# Buck_Converter.net
KiCad netlist of a schematic drawn in Altium Designer
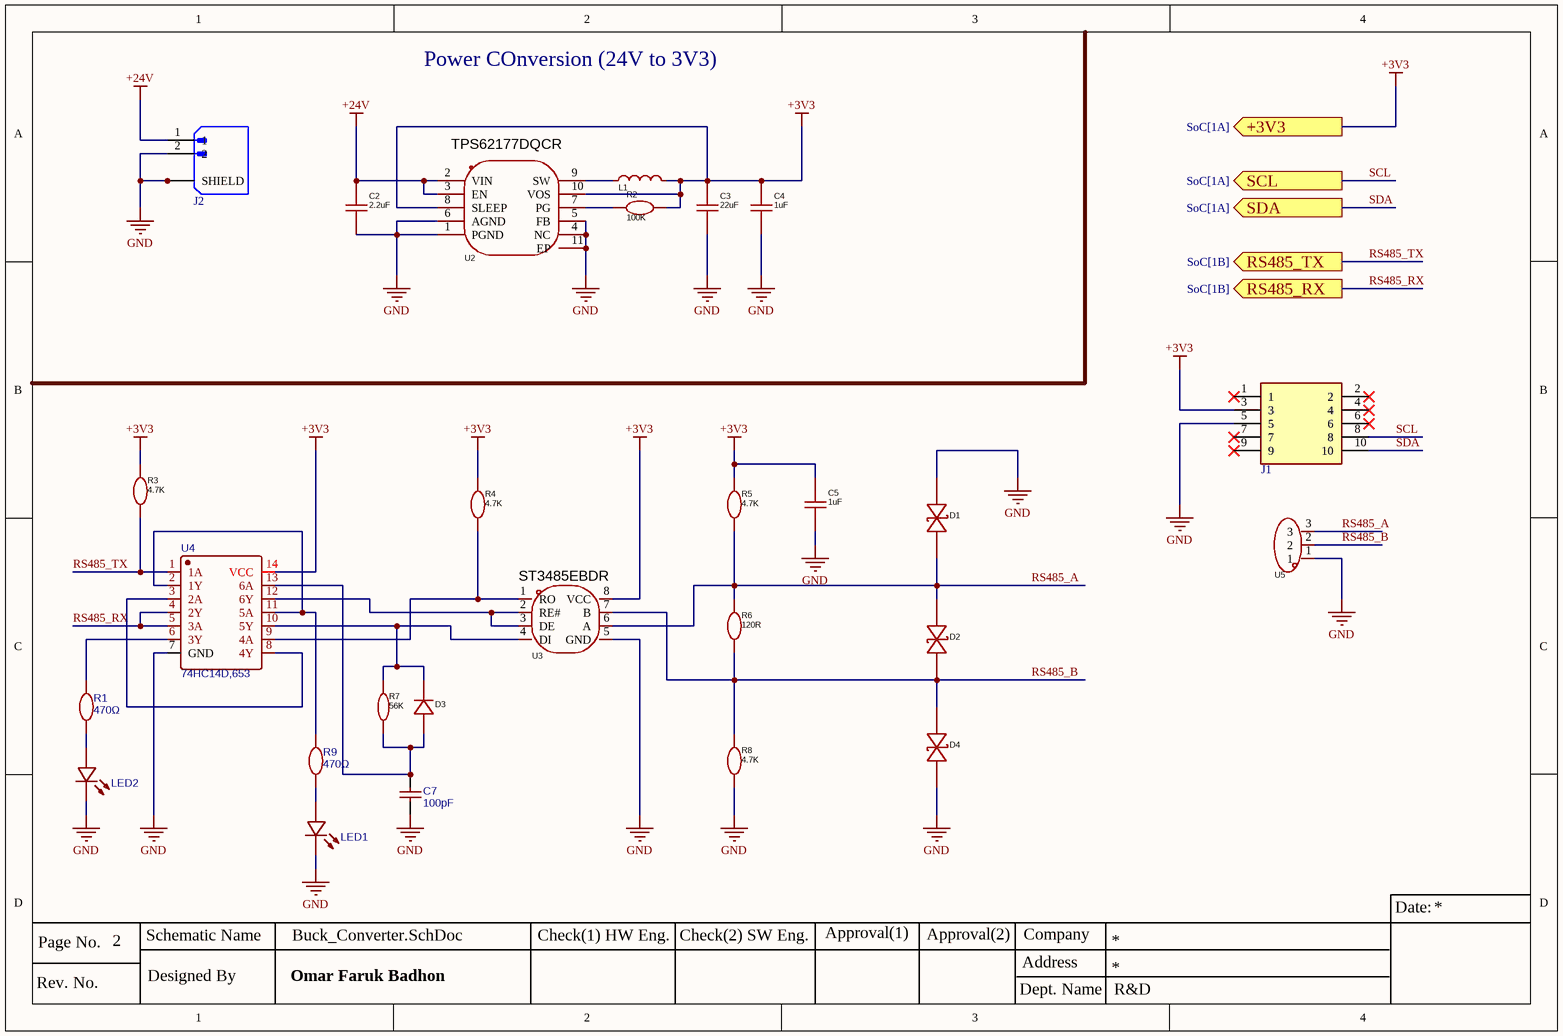
[diagram p0: Buck_Converter.SchDoc]

(export (version "E")
  (design (tool "Eeschema 10.0.6"))
  (components
    (comp (ref "C2")
      (value "2.2uF")
      (footprint "Cap 2.2uF")
      (description "Cap 2.2uF 35V")
      (fields
        (field (name "MANUFACTURER") "muRata(村田)")
        (field (name "MANUFACTURER PART") "GRM155R6YA225KE11D")
      )
      (libsource (lib "Sch lib") (part "GRM155R6YA225KE11D"))
    )
    (comp (ref "C3")
      (value "22uF")
      (footprint "Cap 22uF")
      (description "Cap 22uF 16V")
      (fields
        (field (name "MANUFACTURER") "muRata(村田)")
        (field (name "MANUFACTURER PART") "GRM21BC81C226ME44L")
      )
      (libsource (lib "Sch lib") (part "GRM21BC81C226ME44L"))
    )
    (comp (ref "C4")
      (value "1uF")
      (footprint "Cap 1uF")
      (description "Cap 1uF 16V")
      (fields
        (field (name "MANUFACTURER") "muRata(村田)")
        (field (name "MANUFACTURER PART") "GCM188R71C105KA64D")
      )
      (libsource (lib "Sch lib") (part "GCM188R71C105KA64D"))
    )
    (comp (ref "C5")
      (value "1uF")
      (footprint "Cap 1uF")
      (description "Cap 1uF 16V")
      (fields
        (field (name "MANUFACTURER") "muRata(村田)")
        (field (name "MANUFACTURER PART") "GCM188R71C105KA64D")
      )
      (libsource (lib "Sch lib") (part "GCM188R71C105KA64D"))
    )
    (comp (ref "C7")
      (value "100pF")
      (footprint "Cap 100pF")
      (description "Cap 100pF 50V")
      (fields
        (field (name "MANUFACTURER") "muRata(村田)")
        (field (name "MANUFACTURER PART") "GCM1885C1H101JA16D")
      )
      (libsource (lib "Sch lib") (part "100pF"))
    )
    (comp (ref "D1")
      (value "SMAJ58CA")
      (footprint "TVS diode")
      (fields (field (name "MANUFACTURER") "Littelfuse(美国力特)"))
      (libsource (lib "Sch lib") (part "SMAJ58CA_C148235"))
    )
    (comp (ref "D2")
      (value "SMAJ58CA")
      (footprint "TVS diode")
      (fields (field (name "MANUFACTURER") "Littelfuse(美国力特)"))
      (libsource (lib "Sch lib") (part "SMAJ58CA_C148235"))
    )
    (comp (ref "D3")
      (value "1N4148W")
      (footprint "1N4148W")
      (fields (field (name "MANUFACTURER") "Agertech(艾吉芯)"))
      (libsource (lib "Sch lib") (part "1N4148W"))
    )
    (comp (ref "D4")
      (value "SMAJ58CA")
      (footprint "TVS diode")
      (fields (field (name "MANUFACTURER") "Littelfuse(美国力特)"))
      (libsource (lib "Sch lib") (part "SMAJ58CA_C148235"))
    )
    (comp (ref "J1")
      (value "CLP-105-02-L-D")
      (footprint "Sesnor Connector")
      (libsource (lib "Sch lib") (part "CLP-105-02-L-D"))
    )
    (comp (ref "J2")
      (value "Power Connector")
      (footprint "Power Connector")
      (description "Picoblade Connector, 2 Circuit Single Row, Right Angle Surface Mount SMT PCB")
      (fields (field (name "MF") "{'manufacturer': u'Molex'}") (field (name "MP") "0532610271"))
      (libsource (lib "Sch lib") (part "Power Connector"))
    )
    (comp (ref "L1")
      (value "LPS4018-103MRC")
      (footprint "Inductor")
      (description "Inductor 10uH")
      (fields (field (name "MANUFACTURER") "Coilcraft(线艺)"))
      (libsource (lib "Sch lib") (part "LPS4018-103MRC"))
    )
    (comp (ref "LED1")
      (value "VLMS1300-GS08")
      (footprint "LED")
      (description "Led")
      (fields (field (name "MANUFACTURER") "VISHAY(威世)") (field (name "CONTRIBUTOR") "LCSC"))
      (libsource (lib "Sch lib") (part "VLMS1300-GS08"))
    )
    (comp (ref "LED2")
      (value "VLMS1300-GS08")
      (footprint "LED")
      (description "Led")
      (fields (field (name "MANUFACTURER") "VISHAY(威世)") (field (name "CONTRIBUTOR") "LCSC"))
      (libsource (lib "Sch lib") (part "VLMS1300-GS08"))
    )
    (comp (ref "R1")
      (value "470Ω")
      (footprint "Res 470R")
      (description "Res 470R")
      (fields
        (field (name "MANUFACTURER") "PANASONIC(松下)")
        (field (name "MANUFACTURER PART") "ERJPA3F4700V")
        (field (name "CONTRIBUTOR") "lcsc")
      )
      (libsource (lib "Sch lib") (part "470Ω"))
    )
    (comp (ref "R2")
      (value "100K")
      (footprint "Res 100K")
      (description "Res 100K 50V")
      (fields (field (name "MANUFACTURER") "PANASONIC(松下)") (field (name "MANUFACTURER PART") "ERA2AEB104X"))
      (libsource (lib "Sch lib") (part "ERA2AEB104X"))
    )
    (comp (ref "R3")
      (value "4.7K")
      (footprint "Res 4.7K")
      (description "Res 4.7K")
      (fields (field (name "MANUFACTURER") "PANASONIC(松下)") (field (name "MANUFACTURER PART") "ERJPA3F4701V"))
      (libsource (lib "Sch lib") (part "ERJPA3F4701V"))
    )
    (comp (ref "R4")
      (value "4.7K")
      (footprint "Res 4.7K")
      (description "Res 4.7K")
      (fields (field (name "MANUFACTURER") "PANASONIC(松下)") (field (name "MANUFACTURER PART") "ERJPA3F4701V"))
      (libsource (lib "Sch lib") (part "ERJPA3F4701V"))
    )
    (comp (ref "R5")
      (value "4.7K")
      (footprint "Res 4.7K")
      (description "Res 4.7K")
      (fields (field (name "MANUFACTURER") "PANASONIC(松下)") (field (name "MANUFACTURER PART") "ERJPA3F4701V"))
      (libsource (lib "Sch lib") (part "ERJPA3F4701V"))
    )
    (comp (ref "R6")
      (value "120R")
      (footprint "Res 120R")
      (description "Res 120R")
      (fields (field (name "MANUFACTURER") "PANASONIC(松下)") (field (name "MANUFACTURER PART") "ERJPA3F1200V"))
      (libsource (lib "Sch lib") (part "ERJPA3F1200V"))
    )
    (comp (ref "R7")
      (value "56K")
      (footprint "Rs 56K")
      (description "Res 56K")
      (fields (field (name "MANUFACTURER") "PANASONIC(松下)") (field (name "MANUFACTURER PART") "ERJ3EKF5602V"))
      (libsource (lib "Sch lib") (part "ERJ3EKF5602V"))
    )
    (comp (ref "R8")
      (value "4.7K")
      (footprint "Res 4.7K")
      (description "Res 4.7K")
      (fields (field (name "MANUFACTURER") "PANASONIC(松下)") (field (name "MANUFACTURER PART") "ERJPA3F4701V"))
      (libsource (lib "Sch lib") (part "ERJPA3F4701V"))
    )
    (comp (ref "R9")
      (value "470Ω")
      (footprint "Res 470R")
      (description "Res 470R")
      (fields
        (field (name "MANUFACTURER") "PANASONIC(松下)")
        (field (name "MANUFACTURER PART") "ERJPA3F4700V")
        (field (name "CONTRIBUTOR") "lcsc")
      )
      (libsource (lib "Sch lib") (part "470Ω"))
    )
    (comp (ref "U2")
      (value "TPS62177DQCR")
      (footprint "TPS62177DQCR")
      (fields (field (name "MANUFACTURER") "TI(德州仪器)"))
      (libsource (lib "Sch lib") (part "TPS62177DQCR"))
    )
    (comp (ref "U3")
      (value "ST3485EBDR")
      (footprint "ST3485EBDR")
      (fields (field (name "MANUFACTURER") "ST(意法半导体)"))
      (libsource (lib "Sch lib") (part "ST3485EBDR"))
    )
    (comp (ref "U4")
      (value "74HC14D,653")
      (footprint "74HC14D")
      (fields (field (name "MANUFACTURER") "Nexperia(安世)"))
      (libsource (lib "Sch lib") (part "74HC14D,653"))
    )
    (comp (ref "U5")
      (value "733-363")
      (footprint "RS485 connector")
      (description "6A 3 Straight Needle -60℃~+100℃ 1 2.5mm Gray Plugin,P=2.5mm  Pluggable System Terminal Block ROHS")
      (fields (field (name "MANUFACTURER") "WAGO(万可)"))
      (libsource (lib "Sch lib") (part "RS485 Connector"))
    )
  )
  (nets
    (net (code "1") (name "+3V3") (class "Default")
      (node (ref "C3") (pin "2") (pinfunction "2_2") (pintype "passive"))
      (node (ref "C4") (pin "2") (pinfunction "2_2") (pintype "passive"))
      (node (ref "C5") (pin "2") (pinfunction "2_2") (pintype "passive"))
      (node (ref "J1") (pin "3") (pinfunction "3_3") (pintype "passive"))
      (node (ref "L1") (pin "2") (pinfunction "2_2") (pintype "passive"))
      (node (ref "R2") (pin "2") (pinfunction "2_2") (pintype "passive"))
      (node (ref "R3") (pin "2") (pinfunction "2_2") (pintype "passive"))
      (node (ref "R4") (pin "2") (pinfunction "2_2") (pintype "passive"))
      (node (ref "R5") (pin "2") (pinfunction "2_2") (pintype "passive"))
      (node (ref "U2") (pin "10") (pinfunction "VOS_10") (pintype "passive"))
      (node (ref "U2") (pin "8") (pinfunction "SLEEP_8") (pintype "passive"))
      (node (ref "U3") (pin "8") (pinfunction "VCC_8") (pintype "passive"))
      (node (ref "U4") (pin "14") (pinfunction "VCC_14") (pintype "passive"))
    )
    (net (code "2") (name "+24V") (class "Default")
      (node (ref "C2") (pin "2") (pinfunction "2_2") (pintype "passive"))
      (node (ref "J2") (pin "1") (pinfunction "1_1") (pintype "passive"))
      (node (ref "U2") (pin "2") (pinfunction "VIN_2") (pintype "passive"))
      (node (ref "U2") (pin "3") (pinfunction "EN_3") (pintype "passive"))
    )
    (net (code "3") (name "/RS485_A") (class "Default")
      (node (ref "D1") (pin "1") (pinfunction "1_1") (pintype "passive"))
      (node (ref "D2") (pin "2") (pinfunction "2_2") (pintype "passive"))
      (node (ref "R5") (pin "1") (pinfunction "1_1") (pintype "passive"))
      (node (ref "R6") (pin "2") (pinfunction "2_2") (pintype "passive"))
      (node (ref "U3") (pin "6") (pinfunction "A_6") (pintype "passive"))
      (node (ref "U5") (pin "3") (pinfunction "3_3") (pintype "passive"))
    )
    (net (code "4") (name "/RS485_B") (class "Default")
      (node (ref "D2") (pin "1") (pinfunction "1_1") (pintype "passive"))
      (node (ref "D4") (pin "2") (pinfunction "2_2") (pintype "passive"))
      (node (ref "R6") (pin "1") (pinfunction "1_1") (pintype "passive"))
      (node (ref "R8") (pin "2") (pinfunction "2_2") (pintype "passive"))
      (node (ref "U3") (pin "7") (pinfunction "B_7") (pintype "passive"))
      (node (ref "U5") (pin "2") (pinfunction "2_2") (pintype "passive"))
    )
    (net (code "5") (name "/RS485_RX") (class "Default")
      (node (ref "U4") (pin "4") (pinfunction "2Y_4") (pintype "passive"))
      (node (ref "U4") (pin "5") (pinfunction "3A_5") (pintype "passive"))
    )
    (net (code "6") (name "/RS485_TX") (class "Default")
      (node (ref "R3") (pin "1") (pinfunction "1_1") (pintype "passive"))
      (node (ref "U4") (pin "1") (pinfunction "1A_1") (pintype "passive"))
    )
    (net (code "7") (name "/SCL") (class "Default")
      (node (ref "J1") (pin "8") (pinfunction "8_8") (pintype "passive"))
    )
    (net (code "8") (name "/SDA") (class "Default")
      (node (ref "J1") (pin "10") (pinfunction "10_10") (pintype "passive"))
    )
    (net (code "9") (name "GND") (class "Default")
      (node (ref "C2") (pin "1") (pinfunction "1_1") (pintype "passive"))
      (node (ref "C3") (pin "1") (pinfunction "1_1") (pintype "passive"))
      (node (ref "C4") (pin "1") (pinfunction "1_1") (pintype "passive"))
      (node (ref "C5") (pin "1") (pinfunction "1_1") (pintype "passive"))
      (node (ref "C7") (pin "1") (pinfunction "1_1") (pintype "passive"))
      (node (ref "D1") (pin "2") (pinfunction "2_2") (pintype "passive"))
      (node (ref "D4") (pin "1") (pinfunction "1_1") (pintype "passive"))
      (node (ref "J1") (pin "5") (pinfunction "5_5") (pintype "passive"))
      (node (ref "J2") (pin "2") (pinfunction "2_2") (pintype "passive"))
      (node (ref "J2") (pin "S1") (pinfunction "SHIELD_S1") (pintype "passive"))
      (node (ref "J2") (pin "S2") (pinfunction "SHIELD_S2") (pintype "passive"))
      (node (ref "LED1") (pin "2") (pinfunction "C_2") (pintype "passive"))
      (node (ref "LED2") (pin "2") (pinfunction "C_2") (pintype "passive"))
      (node (ref "R8") (pin "1") (pinfunction "1_1") (pintype "passive"))
      (node (ref "U2") (pin "1") (pinfunction "PGND_1") (pintype "passive"))
      (node (ref "U2") (pin "11") (pinfunction "EP_11") (pintype "passive"))
      (node (ref "U2") (pin "4") (pinfunction "NC_4") (pintype "passive"))
      (node (ref "U2") (pin "5") (pinfunction "FB_5") (pintype "passive"))
      (node (ref "U2") (pin "6") (pinfunction "AGND_6") (pintype "passive"))
      (node (ref "U3") (pin "5") (pinfunction "GND_5") (pintype "passive"))
      (node (ref "U4") (pin "7") (pinfunction "GND_7") (pintype "passive"))
      (node (ref "U5") (pin "1") (pinfunction "1_1") (pintype "passive"))
    )
    (net (code "10") (name "Net-(D3-A)") (class "Default")
      (node (ref "C7") (pin "2") (pinfunction "2_2") (pintype "passive"))
      (node (ref "D3") (pin "2") (pinfunction "A_2") (pintype "passive"))
      (node (ref "R7") (pin "1") (pinfunction "1_1") (pintype "passive"))
      (node (ref "U4") (pin "13") (pinfunction "6A_13") (pintype "passive"))
    )
    (net (code "11") (name "Net-(D3-K)") (class "Default")
      (node (ref "D3") (pin "1") (pinfunction "K_1") (pintype "passive"))
      (node (ref "R7") (pin "2") (pinfunction "2_2") (pintype "passive"))
      (node (ref "U3") (pin "4") (pinfunction "DI_4") (pintype "passive"))
      (node (ref "U4") (pin "10") (pinfunction "5Y_10") (pintype "passive"))
    )
    (net (code "12") (name "Net-(LED1-A)") (class "Default")
      (node (ref "LED1") (pin "1") (pinfunction "A_1") (pintype "passive"))
      (node (ref "R9") (pin "1") (pinfunction "1_1") (pintype "passive"))
    )
    (net (code "13") (name "Net-(LED2-A)") (class "Default")
      (node (ref "LED2") (pin "1") (pinfunction "A_1") (pintype "passive"))
      (node (ref "R1") (pin "1") (pinfunction "1_1") (pintype "passive"))
    )
    (net (code "14") (name "Net-(U2-PG)") (class "Default")
      (node (ref "R2") (pin "1") (pinfunction "1_1") (pintype "passive"))
      (node (ref "U2") (pin "7") (pinfunction "PG_7") (pintype "passive"))
    )
    (net (code "15") (name "Net-(U2-SW)") (class "Default")
      (node (ref "L1") (pin "1") (pinfunction "1_1") (pintype "passive"))
      (node (ref "U2") (pin "9") (pinfunction "SW_9") (pintype "passive"))
    )
    (net (code "16") (name "Net-(U3-DE)") (class "Default")
      (node (ref "U3") (pin "2") (pinfunction "RE#_2") (pintype "passive"))
      (node (ref "U3") (pin "3") (pinfunction "DE_3") (pintype "passive"))
      (node (ref "U4") (pin "12") (pinfunction "6Y_12") (pintype "passive"))
    )
    (net (code "17") (name "Net-(U3-RO)") (class "Default")
      (node (ref "R4") (pin "1") (pinfunction "1_1") (pintype "passive"))
      (node (ref "U3") (pin "1") (pinfunction "RO_1") (pintype "passive"))
      (node (ref "U4") (pin "9") (pinfunction "4A_9") (pintype "passive"))
    )
    (net (code "18") (name "Net-(U4-1Y)") (class "Default")
      (node (ref "R9") (pin "2") (pinfunction "2_2") (pintype "passive"))
      (node (ref "U4") (pin "11") (pinfunction "5A_11") (pintype "passive"))
      (node (ref "U4") (pin "2") (pinfunction "1Y_2") (pintype "passive"))
    )
    (net (code "19") (name "Net-(U4-2A)") (class "Default")
      (node (ref "U4") (pin "3") (pinfunction "2A_3") (pintype "passive"))
      (node (ref "U4") (pin "8") (pinfunction "4Y_8") (pintype "passive"))
    )
    (net (code "20") (name "Net-(U4-3Y)") (class "Default")
      (node (ref "R1") (pin "2") (pinfunction "2_2") (pintype "passive"))
      (node (ref "U4") (pin "6") (pinfunction "3Y_6") (pintype "passive"))
    )
    (net (code "21") (name "unconnected-(J1-Pad1)") (class "Default")
      (node (ref "J1") (pin "1") (pinfunction "1_1") (pintype "passive+no_connect"))
    )
    (net (code "22") (name "unconnected-(J1-Pad2)") (class "Default")
      (node (ref "J1") (pin "2") (pinfunction "2_2") (pintype "passive+no_connect"))
    )
    (net (code "23") (name "unconnected-(J1-Pad4)") (class "Default")
      (node (ref "J1") (pin "4") (pinfunction "4_4") (pintype "passive+no_connect"))
    )
    (net (code "24") (name "unconnected-(J1-Pad6)") (class "Default")
      (node (ref "J1") (pin "6") (pinfunction "6_6") (pintype "passive+no_connect"))
    )
    (net (code "25") (name "unconnected-(J1-Pad7)") (class "Default")
      (node (ref "J1") (pin "7") (pinfunction "7_7") (pintype "passive+no_connect"))
    )
    (net (code "26") (name "unconnected-(J1-Pad9)") (class "Default")
      (node (ref "J1") (pin "9") (pinfunction "9_9") (pintype "passive+no_connect"))
    )
  )
)
